# decawave.net
KiCad netlist of a schematic drawn in Altium Designer
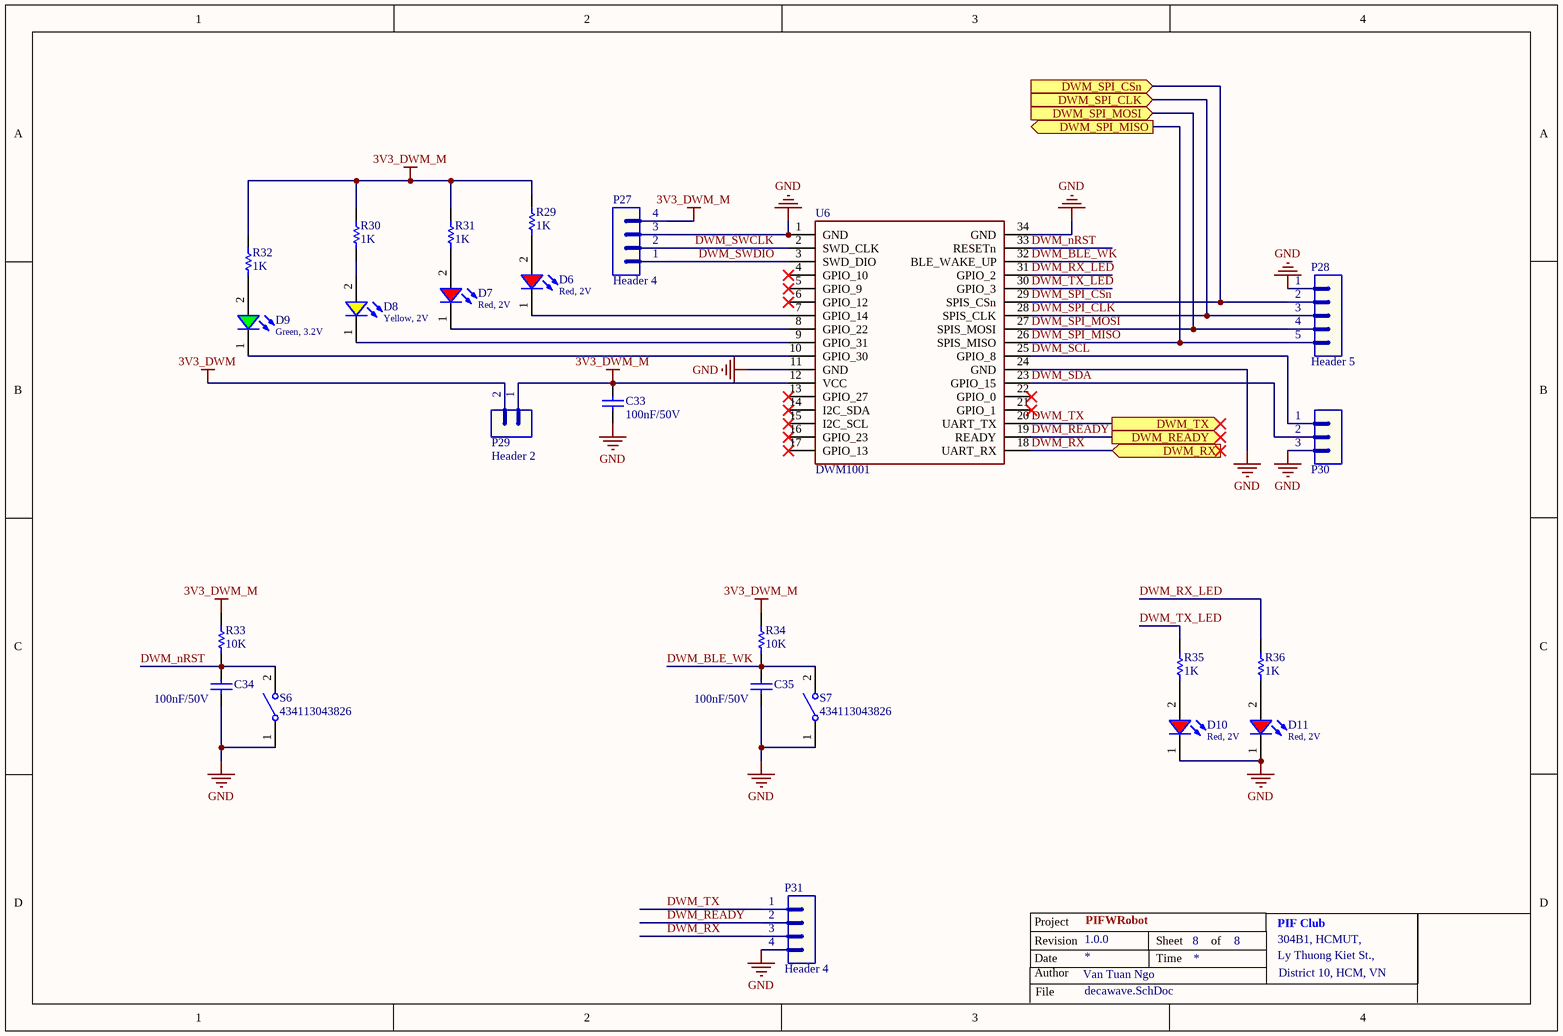
[diagram p0: decawave.SchDoc]

(export (version "E")
  (design (tool "Eeschema 10.0.6"))
  (components
    (comp (ref "C33")
      (value "100nF/50V")
      (footprint "CAP-SM-0805")
      (description "CAP CER 0.1UF 50V Y5V 0805")
      (fields
        (field (name "MANUFACTURER") "Samsung Electro-Mechanics")
        (field (name "MANUFACTURER PART NUMBER") "CL21F104ZBCNNNC")
      )
      (libsource (lib "Capacitor") (part "Cap-100nF-50V-0805"))
    )
    (comp (ref "C34")
      (value "100nF/50V")
      (footprint "CAP-SM-0805")
      (description "CAP CER 0.1UF 50V Y5V 0805")
      (fields
        (field (name "MANUFACTURER") "Samsung Electro-Mechanics")
        (field (name "MANUFACTURER PART NUMBER") "CL21F104ZBCNNNC")
      )
      (libsource (lib "Capacitor") (part "Cap-100nF-50V-0805"))
    )
    (comp (ref "C35")
      (value "100nF/50V")
      (footprint "CAP-SM-0805")
      (description "CAP CER 0.1UF 50V Y5V 0805")
      (fields
        (field (name "MANUFACTURER") "Samsung Electro-Mechanics")
        (field (name "MANUFACTURER PART NUMBER") "CL21F104ZBCNNNC")
      )
      (libsource (lib "Capacitor") (part "Cap-100nF-50V-0805"))
    )
    (comp (ref "D6")
      (value "Red, 2V")
      (footprint "WL-SMCW_0805")
      (description "WL-SMCW SMT Mono-color Chip LED Waterclear, size 0805, Red, 2V, 140deg")
      (fields
        (field (name "PART NUMBER") "150080RS75000")
        (field (name "LOCAL SUPPLIER PARTNUMBER") "x")
        (field (name "PUBLISHER") "Wurth Elektronik")
      )
      (libsource (lib "LED") (part "0805-Red"))
    )
    (comp (ref "D7")
      (value "Red, 2V")
      (footprint "WL-SMCW_0805")
      (description "WL-SMCW SMT Mono-color Chip LED Waterclear, size 0805, Red, 2V, 140deg")
      (fields
        (field (name "PART NUMBER") "150080RS75000")
        (field (name "LOCAL SUPPLIER PARTNUMBER") "x")
        (field (name "PUBLISHER") "Wurth Elektronik")
      )
      (libsource (lib "LED") (part "0805-Red"))
    )
    (comp (ref "D8")
      (value "Yellow, 2V")
      (footprint "WL-SMCW_0805")
      (description "WL-SMCW SMT Mono-color Chip LED Waterclear, size 0805, Yellow, 2V, 140deg")
      (fields
        (field (name "PART NUMBER") "150080YS75000")
        (field (name "LOCAL SUPPLIER PART NUMBER") "x")
        (field (name "PUBLISHER") "Wurth Elektronik")
      )
      (libsource (lib "LED") (part "0805-Yellow"))
    )
    (comp (ref "D9")
      (value "Green, 3.2V")
      (footprint "WL-SMCW_0805")
      (description "WL-SMCW SMT Mono-color Chip LED Waterclear, size 0805, Green, 3.2V, 140deg")
      (fields
        (field (name "PART NUMBER") "150080GS75000")
        (field (name "LOCAL SUPPLIER PART NUMBER") "x")
        (field (name "PUBLISHER") "Wurth Elektronik")
      )
      (libsource (lib "LED") (part "0805-Green"))
    )
    (comp (ref "D10")
      (value "Red, 2V")
      (footprint "WL-SMCW_0805")
      (description "WL-SMCW SMT Mono-color Chip LED Waterclear, size 0805, Red, 2V, 140deg")
      (fields
        (field (name "PART NUMBER") "150080RS75000")
        (field (name "LOCAL SUPPLIER PARTNUMBER") "x")
        (field (name "PUBLISHER") "Wurth Elektronik")
      )
      (libsource (lib "LED") (part "0805-Red"))
    )
    (comp (ref "D11")
      (value "Red, 2V")
      (footprint "WL-SMCW_0805")
      (description "WL-SMCW SMT Mono-color Chip LED Waterclear, size 0805, Red, 2V, 140deg")
      (fields
        (field (name "PART NUMBER") "150080RS75000")
        (field (name "LOCAL SUPPLIER PARTNUMBER") "x")
        (field (name "PUBLISHER") "Wurth Elektronik")
      )
      (libsource (lib "LED") (part "0805-Red"))
    )
    (comp (ref "P27")
      (value "Header 4")
      (footprint "JP4")
      (description "Header, 4-Pin")
      (fields (field (name "LOCAL SUPPLIER PART NUMBER") "x") (field (name "PUBLISHER") "Altium Limited"))
      (libsource (lib "Header-Connector") (part "Header 4"))
    )
    (comp (ref "P28")
      (value "Header 5")
      (footprint "JP5")
      (description "Header, 5-Pin")
      (fields (field (name "LOCAL SUPPLIER PART NUMBER") "x") (field (name "PUBLISHER") "Altium Limited"))
      (libsource (lib "Header-Connector") (part "Header 5"))
    )
    (comp (ref "P29")
      (value "Header 2")
      (footprint "JP2")
      (description "Header, 2-Pin")
      (fields (field (name "LOCAL SUPPLIER PART NUMBER") "x") (field (name "PUBLISHER") "Altium Limited"))
      (libsource (lib "Header-Connector") (part "Header 2"))
    )
    (comp (ref "P30")
      (value "Header 3")
      (footprint "JP3")
      (description "Header, 3-Pin")
      (fields (field (name "LOCAL SUPPLIER PART NUMBER") "x") (field (name "PUBLISHER") "Altium Limited"))
      (libsource (lib "Header-Connector") (part "Header 3"))
    )
    (comp (ref "P31")
      (value "Header 4")
      (footprint "JP4")
      (description "Header, 4-Pin")
      (fields (field (name "LOCAL SUPPLIER PART NUMBER") "x") (field (name "PUBLISHER") "Altium Limited"))
      (libsource (lib "") (part "Header 4_1"))
    )
    (comp (ref "R29")
      (value "1K")
      (footprint "Resistor:RES-SM-0805")
      (description "RES 1K OHM 1% 1/4W 0805")
      (fields
        (field (name "MANUFACTURER") "Stackpole Electronics Inc")
        (field (name "MANUFACTURER PART NUMBER") "RNCP0805FTD1K00")
      )
      (libsource (lib "Resistor") (part "Res-1K-0805"))
    )
    (comp (ref "R30")
      (value "1K")
      (footprint "Resistor:RES-SM-0805")
      (description "RES 1K OHM 1% 1/4W 0805")
      (fields
        (field (name "MANUFACTURER") "Stackpole Electronics Inc")
        (field (name "MANUFACTURER PART NUMBER") "RNCP0805FTD1K00")
      )
      (libsource (lib "Resistor") (part "Res-1K-0805"))
    )
    (comp (ref "R31")
      (value "1K")
      (footprint "Resistor:RES-SM-0805")
      (description "RES 1K OHM 1% 1/4W 0805")
      (fields
        (field (name "MANUFACTURER") "Stackpole Electronics Inc")
        (field (name "MANUFACTURER PART NUMBER") "RNCP0805FTD1K00")
      )
      (libsource (lib "Resistor") (part "Res-1K-0805"))
    )
    (comp (ref "R32")
      (value "1K")
      (footprint "Resistor:RES-SM-0805")
      (description "RES 1K OHM 1% 1/4W 0805")
      (fields
        (field (name "MANUFACTURER") "Stackpole Electronics Inc")
        (field (name "MANUFACTURER PART NUMBER") "RNCP0805FTD1K00")
      )
      (libsource (lib "Resistor") (part "Res-1K-0805"))
    )
    (comp (ref "R33")
      (value "10K")
      (footprint "Resistor:RES-SM-0805")
      (description "RES 10K OHM 1% 1/4W 0805")
      (fields
        (field (name "MANUFACTURER") "Stackpole Electronics Inc")
        (field (name "MANUFACTURER PART NUMBER") "RNCP0805FTD10K0")
      )
      (libsource (lib "Resistor") (part "Res-10k-0805"))
    )
    (comp (ref "R34")
      (value "10K")
      (footprint "Resistor:RES-SM-0805")
      (description "RES 10K OHM 1% 1/4W 0805")
      (fields
        (field (name "MANUFACTURER") "Stackpole Electronics Inc")
        (field (name "MANUFACTURER PART NUMBER") "RNCP0805FTD10K0")
      )
      (libsource (lib "Resistor") (part "Res-10k-0805"))
    )
    (comp (ref "R35")
      (value "1K")
      (footprint "Resistor:RES-SM-0805")
      (description "RES 1K OHM 1% 1/4W 0805")
      (fields
        (field (name "MANUFACTURER") "Stackpole Electronics Inc")
        (field (name "MANUFACTURER PART NUMBER") "RNCP0805FTD1K00")
      )
      (libsource (lib "Resistor") (part "Res-1K-0805"))
    )
    (comp (ref "R36")
      (value "1K")
      (footprint "Resistor:RES-SM-0805")
      (description "RES 1K OHM 1% 1/4W 0805")
      (fields
        (field (name "MANUFACTURER") "Stackpole Electronics Inc")
        (field (name "MANUFACTURER PART NUMBER") "RNCP0805FTD1K00")
      )
      (libsource (lib "Resistor") (part "Res-1K-0805"))
    )
    (comp (ref "S6")
      (value "434113043826")
      (footprint "434113043826")
      (description "WS-TASV J-Bend SMT Tact Switch 6x3.5mm, height 4.3mm, 260gf")
      (fields (field (name "LOCAL SUPPLIER PART NUMBER") "x") (field (name "PUBLISHER") "Wurth Elektronik"))
      (libsource (lib "switch") (part "434113043826"))
    )
    (comp (ref "S7")
      (value "434113043826")
      (footprint "434113043826")
      (description "WS-TASV J-Bend SMT Tact Switch 6x3.5mm, height 4.3mm, 260gf")
      (fields (field (name "LOCAL SUPPLIER PART NUMBER") "x") (field (name "PUBLISHER") "Wurth Elektronik"))
      (libsource (lib "switch") (part "434113043826"))
    )
    (comp (ref "U6")
      (value "DWM1001")
      (footprint "PIFWRobot:DWM1001")
      (fields (field (name "LOCAL SUPPLIER PART NUMBER") "x"))
      (libsource (lib "PIFWRobot") (part "DWM1001"))
    )
  )
  (nets
    (net (code "1") (name "/DWM_BLE_WK") (class "Default")
      (node (ref "C35") (pin "2") (pinfunction "2_2") (pintype "passive"))
      (node (ref "R34") (pin "1") (pinfunction "1_1") (pintype "passive"))
      (node (ref "S7") (pin "2") (pinfunction "2_2") (pintype "passive"))
      (node (ref "U6") (pin "32") (pinfunction "BLE_WAKE_UP_32") (pintype "passive"))
    )
    (net (code "2") (name "/DWM_READY") (class "Default")
      (node (ref "P31") (pin "2") (pinfunction "2_2") (pintype "passive"))
      (node (ref "U6") (pin "19") (pinfunction "READY_19") (pintype "passive"))
    )
    (net (code "3") (name "/DWM_RX") (class "Default")
      (node (ref "P31") (pin "3") (pinfunction "3_3") (pintype "passive"))
      (node (ref "U6") (pin "18") (pinfunction "UART_RX_18") (pintype "passive"))
    )
    (net (code "4") (name "/DWM_RX_LED") (class "Default")
      (node (ref "R36") (pin "2") (pinfunction "2_2") (pintype "passive"))
      (node (ref "U6") (pin "31") (pinfunction "GPIO_2_31") (pintype "passive"))
    )
    (net (code "5") (name "/DWM_SCL") (class "Default")
      (node (ref "P30") (pin "1") (pinfunction "1_1") (pintype "passive"))
      (node (ref "U6") (pin "25") (pinfunction "GPIO_8_25") (pintype "passive"))
    )
    (net (code "6") (name "/DWM_SDA") (class "Default")
      (node (ref "P30") (pin "2") (pinfunction "2_2") (pintype "passive"))
      (node (ref "U6") (pin "23") (pinfunction "GPIO_15_23") (pintype "passive"))
    )
    (net (code "7") (name "/DWM_SPI_CLK") (class "Default")
      (node (ref "P28") (pin "3") (pinfunction "3_3") (pintype "passive"))
      (node (ref "U6") (pin "28") (pinfunction "SPIS_CLK_28") (pintype "passive"))
    )
    (net (code "8") (name "/DWM_SPI_CSn") (class "Default")
      (node (ref "P28") (pin "2") (pinfunction "2_2") (pintype "passive"))
      (node (ref "U6") (pin "29") (pinfunction "SPIS_CSn_29") (pintype "passive"))
    )
    (net (code "9") (name "/DWM_SPI_MISO") (class "Default")
      (node (ref "P28") (pin "5") (pinfunction "5_5") (pintype "passive"))
      (node (ref "U6") (pin "26") (pinfunction "SPIS_MISO_26") (pintype "passive"))
    )
    (net (code "10") (name "/DWM_SPI_MOSI") (class "Default")
      (node (ref "P28") (pin "4") (pinfunction "4_4") (pintype "passive"))
      (node (ref "U6") (pin "27") (pinfunction "SPIS_MOSI_27") (pintype "passive"))
    )
    (net (code "11") (name "/DWM_SWCLK") (class "Default")
      (node (ref "P27") (pin "2") (pinfunction "2_2") (pintype "passive"))
      (node (ref "U6") (pin "2") (pinfunction "SWD_CLK_2") (pintype "passive"))
    )
    (net (code "12") (name "/DWM_SWDIO") (class "Default")
      (node (ref "P27") (pin "1") (pinfunction "1_1") (pintype "passive"))
      (node (ref "U6") (pin "3") (pinfunction "SWD_DIO_3") (pintype "passive"))
    )
    (net (code "13") (name "/DWM_TX") (class "Default")
      (node (ref "P31") (pin "1") (pinfunction "1_1") (pintype "passive"))
      (node (ref "U6") (pin "20") (pinfunction "UART_TX_20") (pintype "passive"))
    )
    (net (code "14") (name "/DWM_TX_LED") (class "Default")
      (node (ref "R35") (pin "2") (pinfunction "2_2") (pintype "passive"))
      (node (ref "U6") (pin "30") (pinfunction "GPIO_3_30") (pintype "passive"))
    )
    (net (code "15") (name "/DWM_nRST") (class "Default")
      (node (ref "C34") (pin "2") (pinfunction "2_2") (pintype "passive"))
      (node (ref "R33") (pin "1") (pinfunction "1_1") (pintype "passive"))
      (node (ref "S6") (pin "2") (pinfunction "2_2") (pintype "passive"))
      (node (ref "U6") (pin "33") (pinfunction "RESETn_33") (pintype "passive"))
    )
    (net (code "16") (name "3V3_DWM") (class "Default")
      (node (ref "P29") (pin "2") (pinfunction "2_2") (pintype "passive"))
    )
    (net (code "17") (name "3V3_DWM_M") (class "Default")
      (node (ref "C33") (pin "2") (pinfunction "2_2") (pintype "passive"))
      (node (ref "P27") (pin "4") (pinfunction "4_4") (pintype "passive"))
      (node (ref "P29") (pin "1") (pinfunction "1_1") (pintype "passive"))
      (node (ref "R29") (pin "2") (pinfunction "2_2") (pintype "passive"))
      (node (ref "R30") (pin "2") (pinfunction "2_2") (pintype "passive"))
      (node (ref "R31") (pin "2") (pinfunction "2_2") (pintype "passive"))
      (node (ref "R32") (pin "2") (pinfunction "2_2") (pintype "passive"))
      (node (ref "R33") (pin "2") (pinfunction "2_2") (pintype "passive"))
      (node (ref "R34") (pin "2") (pinfunction "2_2") (pintype "passive"))
      (node (ref "U6") (pin "12") (pinfunction "VCC_12") (pintype "passive"))
    )
    (net (code "18") (name "GND") (class "Default")
      (node (ref "C33") (pin "1") (pinfunction "1_1") (pintype "passive"))
      (node (ref "C34") (pin "1") (pinfunction "1_1") (pintype "passive"))
      (node (ref "C35") (pin "1") (pinfunction "1_1") (pintype "passive"))
      (node (ref "D10") (pin "1") (pinfunction "K_1") (pintype "passive"))
      (node (ref "D11") (pin "1") (pinfunction "K_1") (pintype "passive"))
      (node (ref "P27") (pin "3") (pinfunction "3_3") (pintype "passive"))
      (node (ref "P28") (pin "1") (pinfunction "1_1") (pintype "passive"))
      (node (ref "P30") (pin "3") (pinfunction "3_3") (pintype "passive"))
      (node (ref "P31") (pin "4") (pinfunction "4_4") (pintype "passive"))
      (node (ref "S6") (pin "1") (pinfunction "1_1") (pintype "passive"))
      (node (ref "S7") (pin "1") (pinfunction "1_1") (pintype "passive"))
      (node (ref "U6") (pin "1") (pinfunction "GND_1") (pintype "passive"))
      (node (ref "U6") (pin "11") (pinfunction "GND_11") (pintype "passive"))
      (node (ref "U6") (pin "24") (pinfunction "GND_24") (pintype "passive"))
      (node (ref "U6") (pin "34") (pinfunction "GND_34") (pintype "passive"))
    )
    (net (code "19") (name "Net-(D6-A)") (class "Default")
      (node (ref "D6") (pin "2") (pinfunction "A_2") (pintype "passive"))
      (node (ref "R29") (pin "1") (pinfunction "1_1") (pintype "passive"))
    )
    (net (code "20") (name "Net-(D6-K)") (class "Default")
      (node (ref "D6") (pin "1") (pinfunction "K_1") (pintype "passive"))
      (node (ref "U6") (pin "7") (pinfunction "GPIO_14_7") (pintype "passive"))
    )
    (net (code "21") (name "Net-(D7-A)") (class "Default")
      (node (ref "D7") (pin "2") (pinfunction "A_2") (pintype "passive"))
      (node (ref "R31") (pin "1") (pinfunction "1_1") (pintype "passive"))
    )
    (net (code "22") (name "Net-(D7-K)") (class "Default")
      (node (ref "D7") (pin "1") (pinfunction "K_1") (pintype "passive"))
      (node (ref "U6") (pin "8") (pinfunction "GPIO_22_8") (pintype "passive"))
    )
    (net (code "23") (name "Net-(D8-A)") (class "Default")
      (node (ref "D8") (pin "2") (pinfunction "A_2") (pintype "passive"))
      (node (ref "R30") (pin "1") (pinfunction "1_1") (pintype "passive"))
    )
    (net (code "24") (name "Net-(D8-K)") (class "Default")
      (node (ref "D8") (pin "1") (pinfunction "K_1") (pintype "passive"))
      (node (ref "U6") (pin "9") (pinfunction "GPIO_31_9") (pintype "passive"))
    )
    (net (code "25") (name "Net-(D9-A)") (class "Default")
      (node (ref "D9") (pin "2") (pinfunction "A_2") (pintype "passive"))
      (node (ref "R32") (pin "1") (pinfunction "1_1") (pintype "passive"))
    )
    (net (code "26") (name "Net-(D9-K)") (class "Default")
      (node (ref "D9") (pin "1") (pinfunction "K_1") (pintype "passive"))
      (node (ref "U6") (pin "10") (pinfunction "GPIO_30_10") (pintype "passive"))
    )
    (net (code "27") (name "Net-(D10-A)") (class "Default")
      (node (ref "D10") (pin "2") (pinfunction "A_2") (pintype "passive"))
      (node (ref "R35") (pin "1") (pinfunction "1_1") (pintype "passive"))
    )
    (net (code "28") (name "Net-(D11-A)") (class "Default")
      (node (ref "D11") (pin "2") (pinfunction "A_2") (pintype "passive"))
      (node (ref "R36") (pin "1") (pinfunction "1_1") (pintype "passive"))
    )
    (net (code "29") (name "unconnected-(U6-GPIO_0-Pad22)") (class "Default")
      (node (ref "U6") (pin "22") (pinfunction "GPIO_0_22") (pintype "passive+no_connect"))
    )
    (net (code "30") (name "unconnected-(U6-GPIO_1-Pad21)") (class "Default")
      (node (ref "U6") (pin "21") (pinfunction "GPIO_1_21") (pintype "passive+no_connect"))
    )
    (net (code "31") (name "unconnected-(U6-GPIO_9-Pad5)") (class "Default")
      (node (ref "U6") (pin "5") (pinfunction "GPIO_9_5") (pintype "passive+no_connect"))
    )
    (net (code "32") (name "unconnected-(U6-GPIO_10-Pad4)") (class "Default")
      (node (ref "U6") (pin "4") (pinfunction "GPIO_10_4") (pintype "passive+no_connect"))
    )
    (net (code "33") (name "unconnected-(U6-GPIO_12-Pad6)") (class "Default")
      (node (ref "U6") (pin "6") (pinfunction "GPIO_12_6") (pintype "passive+no_connect"))
    )
    (net (code "34") (name "unconnected-(U6-GPIO_13-Pad17)") (class "Default")
      (node (ref "U6") (pin "17") (pinfunction "GPIO_13_17") (pintype "passive+no_connect"))
    )
    (net (code "35") (name "unconnected-(U6-GPIO_23-Pad16)") (class "Default")
      (node (ref "U6") (pin "16") (pinfunction "GPIO_23_16") (pintype "passive+no_connect"))
    )
    (net (code "36") (name "unconnected-(U6-GPIO_27-Pad13)") (class "Default")
      (node (ref "U6") (pin "13") (pinfunction "GPIO_27_13") (pintype "passive+no_connect"))
    )
    (net (code "37") (name "unconnected-(U6-I2C_SCL-Pad15)") (class "Default")
      (node (ref "U6") (pin "15") (pinfunction "I2C_SCL_15") (pintype "passive+no_connect"))
    )
    (net (code "38") (name "unconnected-(U6-I2C_SDA-Pad14)") (class "Default")
      (node (ref "U6") (pin "14") (pinfunction "I2C_SDA_14") (pintype "passive+no_connect"))
    )
  )
)
